# 2017_CARTE_PUISSANCE.net
KiCad netlist of a schematic drawn in Altium Designer
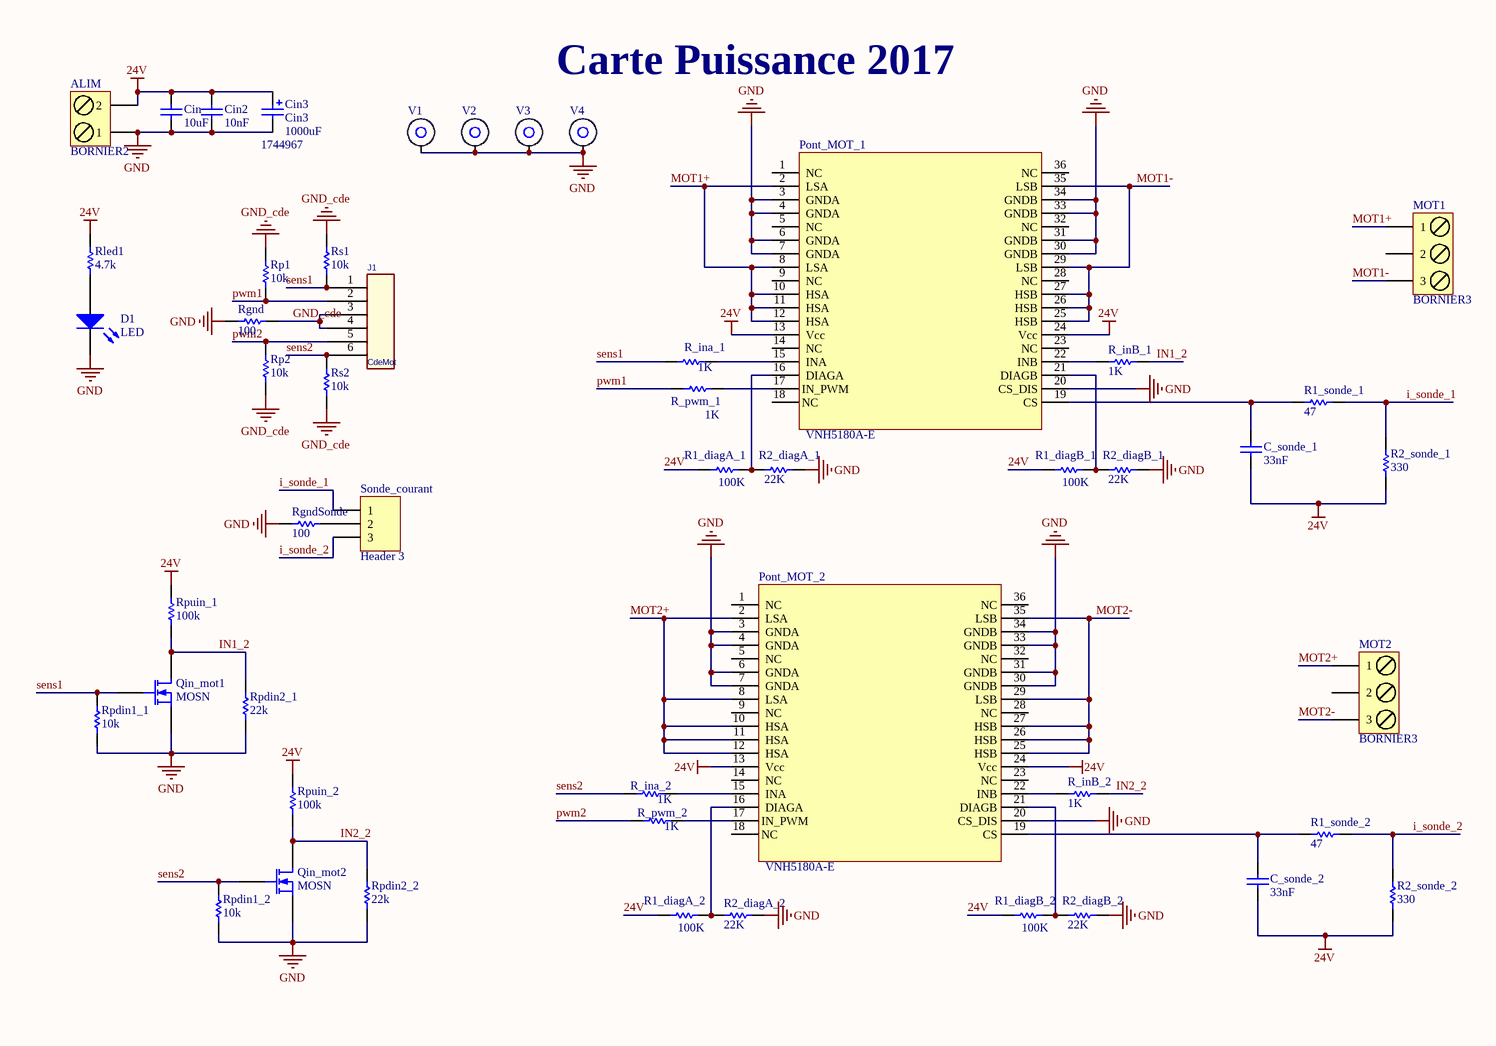
[diagram p0: 2017_CARTE_PUISSANCE.SchDoc, left]
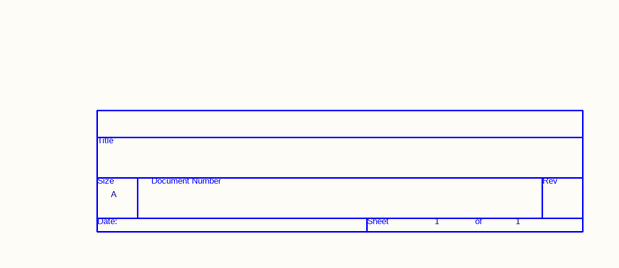
[diagram p1: 2017_CARTE_PUISSANCE.SchDoc, right]

(export (version "E")
  (design (tool "Eeschema 10.0.6"))
  (components
    (comp (ref "*")
      (value "TitleBlock0")
      (fields (field (name "PAGE COUNT") "1") (field (name "PAGE NUMBER") "1") (field (name "PAGE SIZE") "A"))
      (libsource (lib "*") (part "TitleBlock0"))
    )
    (comp (ref "ALIM")
      (value "BORNIER2")
      (footprint "BORNIER2_MALE_DROIT")
      (description "Terminal blocks, 2 pins, pitch=5mm")
      (libsource (lib "Robot2010") (part "BORNIER2"))
    )
    (comp (ref "Cin")
      (value "10uF")
      (footprint "C1206_N")
      (description "Capacitor")
      (fields (field (name "PUBLISHER") "Altium Limited"))
      (libsource (lib "DG_Condensateur") (part "Capacitor"))
    )
    (comp (ref "Cin2")
      (value "10nF")
      (footprint "C0805_N")
      (description "Capacitor")
      (fields (field (name "PUBLISHER") "Altium Limited"))
      (libsource (lib "DG_Condensateur") (part "Capacitor"))
    )
    (comp (ref "Cin3")
      (value "Cin3")
      (footprint "COND_POL_RAD_5.08B")
      (description "Polarized Capacitor")
      (fields
        (field (name "ALTIUM_VALUE") "1000uF")
        (field (name "FAR") "1744967")
        (field (name "PUBLISHER") "Altium Limited")
      )
      (libsource (lib "Robot2010") (part "CONDENSATEUR_POLARISE"))
    )
    (comp (ref "C_sonde_1")
      (value "33nF")
      (footprint "C0603_N")
      (description "Capacitor")
      (fields (field (name "PUBLISHER") "Altium Limited"))
      (libsource (lib "_ROBOT") (part "Condensateur"))
    )
    (comp (ref "C_sonde_2")
      (value "33nF")
      (footprint "C0603_N")
      (description "Capacitor")
      (fields (field (name "PUBLISHER") "Altium Limited"))
      (libsource (lib "_ROBOT") (part "Condensateur"))
    )
    (comp (ref "D1")
      (value "LED")
      (footprint "LED_0805")
      (description "Typical LED")
      (fields (field (name "PUBLISHER") "Altium Limited"))
      (libsource (lib "DG_LED") (part "LED"))
    )
    (comp (ref "J1") (value "CdeMot") (footprint "RJ11_6/6") (libsource (lib "*") (part "CONNECTEUR_RJ12")))
    (comp (ref "MOT1")
      (value "BORNIER3")
      (footprint "BORNIER3")
      (description "Terminal blocks, 2 pins, pitch=5mm")
      (libsource (lib "Connecteur") (part "BORNIER3"))
    )
    (comp (ref "MOT2")
      (value "BORNIER3")
      (footprint "BORNIER3")
      (description "Terminal blocks, 2 pins, pitch=5mm")
      (libsource (lib "Connecteur") (part "BORNIER3"))
    )
    (comp (ref "Pont_MOT_1")
      (value "VNH5180A-E")
      (footprint "PowerSSO-36 TP")
      (fields (field (name "TYPE") "VNH5180A-E"))
      (libsource (lib "Circuit intégré") (part "VNH5180A-E"))
    )
    (comp (ref "Pont_MOT_2")
      (value "VNH5180A-E")
      (footprint "PowerSSO-36 TP")
      (fields (field (name "TYPE") "VNH5180A-E"))
      (libsource (lib "Circuit intégré") (part "VNH5180A-E"))
    )
    (comp (ref "Qin_mot1")
      (value "MOSN")
      (footprint "SOT23-3N")
      (description "N-Channel MOSFET")
      (fields (field (name "PUBLISHER") "Altium Limited"))
      (libsource (lib "_ROBOT") (part "Transistor MOSFET-N"))
    )
    (comp (ref "Qin_mot2")
      (value "MOSN")
      (footprint "SOT23-3N")
      (description "N-Channel MOSFET")
      (fields (field (name "PUBLISHER") "Altium Limited"))
      (libsource (lib "_ROBOT") (part "Transistor MOSFET-N"))
    )
    (comp (ref "R1_diagA_1")
      (value "100K")
      (footprint "R1206_N")
      (description "Resistor")
      (fields (field (name "PUBLISHER") "Altium Limited"))
      (libsource (lib "_ROBOT") (part "Resistor"))
    )
    (comp (ref "R1_diagA_2")
      (value "100K")
      (footprint "R1206_N")
      (description "Resistor")
      (fields (field (name "PUBLISHER") "Altium Limited"))
      (libsource (lib "_ROBOT") (part "Resistor"))
    )
    (comp (ref "R1_diagB_1")
      (value "100K")
      (footprint "R1206_N")
      (description "Resistor")
      (fields (field (name "PUBLISHER") "Altium Limited"))
      (libsource (lib "_ROBOT") (part "Resistor"))
    )
    (comp (ref "R1_diagB_2")
      (value "100K")
      (footprint "R1206_N")
      (description "Resistor")
      (fields (field (name "PUBLISHER") "Altium Limited"))
      (libsource (lib "_ROBOT") (part "Resistor"))
    )
    (comp (ref "R1_sonde_1")
      (value "47")
      (footprint "R1206_N")
      (description "Resistor")
      (fields (field (name "PUBLISHER") "Altium Limited"))
      (libsource (lib "_ROBOT") (part "Resistor"))
    )
    (comp (ref "R1_sonde_2")
      (value "47")
      (footprint "R1206_N")
      (description "Resistor")
      (fields (field (name "PUBLISHER") "Altium Limited"))
      (libsource (lib "_ROBOT") (part "Resistor"))
    )
    (comp (ref "R2_diagA_1")
      (value "22K")
      (footprint "R1206_N")
      (description "Resistor")
      (fields (field (name "PUBLISHER") "Altium Limited"))
      (libsource (lib "_ROBOT") (part "Resistor"))
    )
    (comp (ref "R2_diagA_2")
      (value "22K")
      (footprint "R1206_N")
      (description "Resistor")
      (fields (field (name "PUBLISHER") "Altium Limited"))
      (libsource (lib "_ROBOT") (part "Resistor"))
    )
    (comp (ref "R2_diagB_1")
      (value "22K")
      (footprint "R1206_N")
      (description "Resistor")
      (fields (field (name "PUBLISHER") "Altium Limited"))
      (libsource (lib "_ROBOT") (part "Resistor"))
    )
    (comp (ref "R2_diagB_2")
      (value "22K")
      (footprint "R1206_N")
      (description "Resistor")
      (fields (field (name "PUBLISHER") "Altium Limited"))
      (libsource (lib "_ROBOT") (part "Resistor"))
    )
    (comp (ref "R2_sonde_1")
      (value "330")
      (footprint "R1206_N")
      (description "Resistor")
      (fields (field (name "PUBLISHER") "Altium Limited"))
      (libsource (lib "_ROBOT") (part "Resistor"))
    )
    (comp (ref "R2_sonde_2")
      (value "330")
      (footprint "R1206_N")
      (description "Resistor")
      (fields (field (name "PUBLISHER") "Altium Limited"))
      (libsource (lib "_ROBOT") (part "Resistor"))
    )
    (comp (ref "Rgnd")
      (value "100")
      (footprint "R1206_N")
      (description "Resistor")
      (fields (field (name "PUBLISHER") "Altium Limited"))
      (libsource (lib "DG_Resistance") (part "Resistor"))
    )
    (comp (ref "RgndSonde")
      (value "100")
      (footprint "R1206_N")
      (description "Resistor")
      (fields (field (name "PUBLISHER") "Altium Limited"))
      (libsource (lib "DG_Resistance") (part "Resistor"))
    )
    (comp (ref "Rled1")
      (value "4.7k")
      (footprint "R1206_N")
      (description "Resistor")
      (fields (field (name "PUBLISHER") "Altium Limited"))
      (libsource (lib "DG_Resistance") (part "Resistor"))
    )
    (comp (ref "Rp1")
      (value "10k")
      (footprint "R1206_N")
      (description "Resistor")
      (fields (field (name "PUBLISHER") "Altium Limited"))
      (libsource (lib "DG_Resistance") (part "Resistor"))
    )
    (comp (ref "Rp2")
      (value "10k")
      (footprint "R1206_N")
      (description "Resistor")
      (fields (field (name "PUBLISHER") "Altium Limited"))
      (libsource (lib "DG_Resistance") (part "Resistor"))
    )
    (comp (ref "Rpdin1_1")
      (value "10k")
      (footprint "R1206_N")
      (description "Resistor")
      (fields (field (name "PUBLISHER") "Altium Limited"))
      (libsource (lib "DG_Resistance") (part "Resistor"))
    )
    (comp (ref "Rpdin1_2")
      (value "10k")
      (footprint "R1206_N")
      (description "Resistor")
      (fields (field (name "PUBLISHER") "Altium Limited"))
      (libsource (lib "DG_Resistance") (part "Resistor"))
    )
    (comp (ref "Rpdin2_1")
      (value "22k")
      (footprint "R1206_N")
      (description "Resistor")
      (fields (field (name "PUBLISHER") "Altium Limited"))
      (libsource (lib "DG_Resistance") (part "Resistor"))
    )
    (comp (ref "Rpdin2_2")
      (value "22k")
      (footprint "R1206_N")
      (description "Resistor")
      (fields (field (name "PUBLISHER") "Altium Limited"))
      (libsource (lib "DG_Resistance") (part "Resistor"))
    )
    (comp (ref "Rpuin_1")
      (value "100k")
      (footprint "R1206_N")
      (description "Resistor")
      (fields (field (name "PUBLISHER") "Altium Limited"))
      (libsource (lib "DG_Resistance") (part "Resistor"))
    )
    (comp (ref "Rpuin_2")
      (value "100k")
      (footprint "R1206_N")
      (description "Resistor")
      (fields (field (name "PUBLISHER") "Altium Limited"))
      (libsource (lib "DG_Resistance") (part "Resistor"))
    )
    (comp (ref "Rs1")
      (value "10k")
      (footprint "R1206_N")
      (description "Resistor")
      (fields (field (name "PUBLISHER") "Altium Limited"))
      (libsource (lib "DG_Resistance") (part "Resistor"))
    )
    (comp (ref "Rs2")
      (value "10k")
      (footprint "R1206_N")
      (description "Resistor")
      (fields (field (name "PUBLISHER") "Altium Limited"))
      (libsource (lib "DG_Resistance") (part "Resistor"))
    )
    (comp (ref "R_ina_1")
      (value "1K")
      (footprint "R1206_N")
      (description "Resistor")
      (fields (field (name "PUBLISHER") "Altium Limited"))
      (libsource (lib "_ROBOT") (part "Resistor"))
    )
    (comp (ref "R_ina_2")
      (value "1K")
      (footprint "R1206_N")
      (description "Resistor")
      (fields (field (name "PUBLISHER") "Altium Limited"))
      (libsource (lib "_ROBOT") (part "Resistor"))
    )
    (comp (ref "R_inB_1")
      (value "1K")
      (footprint "R1206_N")
      (description "Resistor")
      (fields (field (name "PUBLISHER") "Altium Limited"))
      (libsource (lib "_ROBOT") (part "Resistor"))
    )
    (comp (ref "R_inB_2")
      (value "1K")
      (footprint "R1206_N")
      (description "Resistor")
      (fields (field (name "PUBLISHER") "Altium Limited"))
      (libsource (lib "_ROBOT") (part "Resistor"))
    )
    (comp (ref "R_pwm_1")
      (value "1K")
      (footprint "R1206_N")
      (description "Resistor")
      (fields (field (name "PUBLISHER") "Altium Limited"))
      (libsource (lib "_ROBOT") (part "Resistor"))
    )
    (comp (ref "R_pwm_2")
      (value "1K")
      (footprint "R1206_N")
      (description "Resistor")
      (fields (field (name "PUBLISHER") "Altium Limited"))
      (libsource (lib "_ROBOT") (part "Resistor"))
    )
    (comp (ref "Sonde_courant")
      (value "Header 3")
      (footprint "HDR1X3")
      (description "Header, 3-Pin")
      (fields (field (name "PUBLISHER") "Altium Limited"))
      (libsource (lib "DG_Connecteur") (part "Header 3"))
    )
    (comp (ref "V1")
      (value "Entretoise WURTH CMS")
      (footprint "ENTRETOISE_CMS")
      (description "Entretoise Wurth")
      (fields (field (name "PUBLISHER") "Damien Guitton"))
      (libsource (lib "_ROBOT") (part "Entretoise WURTH CMS"))
    )
    (comp (ref "V2")
      (value "Entretoise WURTH CMS")
      (footprint "ENTRETOISE_CMS")
      (description "Entretoise Wurth")
      (fields (field (name "PUBLISHER") "Damien Guitton"))
      (libsource (lib "_ROBOT") (part "Entretoise WURTH CMS"))
    )
    (comp (ref "V3")
      (value "Entretoise WURTH CMS")
      (footprint "ENTRETOISE_CMS")
      (description "Entretoise Wurth")
      (fields (field (name "PUBLISHER") "Damien Guitton"))
      (libsource (lib "_ROBOT") (part "Entretoise WURTH CMS"))
    )
    (comp (ref "V4")
      (value "Entretoise WURTH CMS")
      (footprint "ENTRETOISE_CMS")
      (description "Entretoise Wurth")
      (fields (field (name "PUBLISHER") "Damien Guitton"))
      (libsource (lib "_ROBOT") (part "Entretoise WURTH CMS"))
    )
  )
  (nets
    (net (code "1") (name "/IN1_2") (class "Default")
      (node (ref "Qin_mot1") (pin "3") (pinfunction "D_3") (pintype "passive"))
      (node (ref "R_inB_1") (pin "2") (pinfunction "2_2") (pintype "passive"))
      (node (ref "Rpdin2_1") (pin "2") (pinfunction "2_2") (pintype "passive"))
      (node (ref "Rpuin_1") (pin "1") (pinfunction "1_1") (pintype "passive"))
    )
    (net (code "2") (name "/IN2_2") (class "Default")
      (node (ref "Qin_mot2") (pin "3") (pinfunction "D_3") (pintype "passive"))
      (node (ref "R_inB_2") (pin "2") (pinfunction "2_2") (pintype "passive"))
      (node (ref "Rpdin2_2") (pin "2") (pinfunction "2_2") (pintype "passive"))
      (node (ref "Rpuin_2") (pin "1") (pinfunction "1_1") (pintype "passive"))
    )
    (net (code "3") (name "/MOT1+") (class "Default")
      (node (ref "MOT1") (pin "1") (pinfunction "1_1") (pintype "passive"))
      (node (ref "Pont_MOT_1") (pin "10") (pinfunction "HSA_10") (pintype "passive"))
      (node (ref "Pont_MOT_1") (pin "11") (pinfunction "HSA_11") (pintype "passive"))
      (node (ref "Pont_MOT_1") (pin "12") (pinfunction "HSA_12") (pintype "passive"))
      (node (ref "Pont_MOT_1") (pin "2") (pinfunction "LSA_2") (pintype "passive"))
      (node (ref "Pont_MOT_1") (pin "8") (pinfunction "LSA_8") (pintype "passive"))
    )
    (net (code "4") (name "/MOT1-") (class "Default")
      (node (ref "MOT1") (pin "3") (pinfunction "3_3") (pintype "passive"))
      (node (ref "Pont_MOT_1") (pin "25") (pinfunction "HSB_25") (pintype "passive"))
      (node (ref "Pont_MOT_1") (pin "26") (pinfunction "HSB_26") (pintype "passive"))
      (node (ref "Pont_MOT_1") (pin "27") (pinfunction "HSB_27") (pintype "passive"))
      (node (ref "Pont_MOT_1") (pin "29") (pinfunction "LSB_29") (pintype "passive"))
      (node (ref "Pont_MOT_1") (pin "35") (pinfunction "LSB_35") (pintype "passive"))
    )
    (net (code "5") (name "/MOT2+") (class "Default")
      (node (ref "MOT2") (pin "1") (pinfunction "1_1") (pintype "passive"))
      (node (ref "Pont_MOT_2") (pin "10") (pinfunction "HSA_10") (pintype "passive"))
      (node (ref "Pont_MOT_2") (pin "11") (pinfunction "HSA_11") (pintype "passive"))
      (node (ref "Pont_MOT_2") (pin "12") (pinfunction "HSA_12") (pintype "passive"))
      (node (ref "Pont_MOT_2") (pin "2") (pinfunction "LSA_2") (pintype "passive"))
      (node (ref "Pont_MOT_2") (pin "8") (pinfunction "LSA_8") (pintype "passive"))
    )
    (net (code "6") (name "/MOT2-") (class "Default")
      (node (ref "MOT2") (pin "3") (pinfunction "3_3") (pintype "passive"))
      (node (ref "Pont_MOT_2") (pin "25") (pinfunction "HSB_25") (pintype "passive"))
      (node (ref "Pont_MOT_2") (pin "26") (pinfunction "HSB_26") (pintype "passive"))
      (node (ref "Pont_MOT_2") (pin "27") (pinfunction "HSB_27") (pintype "passive"))
      (node (ref "Pont_MOT_2") (pin "29") (pinfunction "LSB_29") (pintype "passive"))
      (node (ref "Pont_MOT_2") (pin "35") (pinfunction "LSB_35") (pintype "passive"))
    )
    (net (code "7") (name "/i_sonde_1") (class "Default")
      (node (ref "R1_sonde_1") (pin "2") (pinfunction "2_2") (pintype "passive"))
      (node (ref "R2_sonde_1") (pin "2") (pinfunction "2_2") (pintype "passive"))
      (node (ref "Sonde_courant") (pin "1") (pinfunction "1_1") (pintype "passive"))
    )
    (net (code "8") (name "/i_sonde_2") (class "Default")
      (node (ref "R1_sonde_2") (pin "2") (pinfunction "2_2") (pintype "passive"))
      (node (ref "R2_sonde_2") (pin "2") (pinfunction "2_2") (pintype "passive"))
      (node (ref "Sonde_courant") (pin "3") (pinfunction "3_3") (pintype "passive"))
    )
    (net (code "9") (name "/pwm1") (class "Default")
      (node (ref "J1") (pin "2") (pinfunction "2_2") (pintype "passive"))
      (node (ref "R_pwm_1") (pin "1") (pinfunction "1_1") (pintype "passive"))
      (node (ref "Rp1") (pin "1") (pinfunction "1_1") (pintype "passive"))
    )
    (net (code "10") (name "/pwm2") (class "Default")
      (node (ref "J1") (pin "5") (pinfunction "5_5") (pintype "passive"))
      (node (ref "R_pwm_2") (pin "1") (pinfunction "1_1") (pintype "passive"))
      (node (ref "Rp2") (pin "2") (pinfunction "2_2") (pintype "passive"))
    )
    (net (code "11") (name "/sens1") (class "Default")
      (node (ref "J1") (pin "1") (pinfunction "1_1") (pintype "passive"))
      (node (ref "Qin_mot1") (pin "1") (pinfunction "G_1") (pintype "passive"))
      (node (ref "R_ina_1") (pin "1") (pinfunction "1_1") (pintype "passive"))
      (node (ref "Rpdin1_1") (pin "1") (pinfunction "1_1") (pintype "passive"))
      (node (ref "Rs1") (pin "1") (pinfunction "1_1") (pintype "passive"))
    )
    (net (code "12") (name "/sens2") (class "Default")
      (node (ref "J1") (pin "6") (pinfunction "6_6") (pintype "passive"))
      (node (ref "Qin_mot2") (pin "1") (pinfunction "G_1") (pintype "passive"))
      (node (ref "R_ina_2") (pin "1") (pinfunction "1_1") (pintype "passive"))
      (node (ref "Rpdin1_2") (pin "1") (pinfunction "1_1") (pintype "passive"))
      (node (ref "Rs2") (pin "2") (pinfunction "2_2") (pintype "passive"))
    )
    (net (code "13") (name "24V") (class "Default")
      (node (ref "ALIM") (pin "2") (pinfunction "2_2") (pintype "passive"))
      (node (ref "C_sonde_1") (pin "1") (pinfunction "1_1") (pintype "passive"))
      (node (ref "C_sonde_2") (pin "1") (pinfunction "1_1") (pintype "passive"))
      (node (ref "Cin") (pin "2") (pinfunction "2_2") (pintype "passive"))
      (node (ref "Cin2") (pin "2") (pinfunction "2_2") (pintype "passive"))
      (node (ref "Cin3") (pin "1") (pinfunction "1_1") (pintype "passive"))
      (node (ref "Pont_MOT_1") (pin "13") (pinfunction "Vcc_13") (pintype "passive"))
      (node (ref "Pont_MOT_1") (pin "24") (pinfunction "Vcc_24") (pintype "passive"))
      (node (ref "Pont_MOT_2") (pin "13") (pinfunction "Vcc_13") (pintype "passive"))
      (node (ref "Pont_MOT_2") (pin "24") (pinfunction "Vcc_24") (pintype "passive"))
      (node (ref "R1_diagA_1") (pin "1") (pinfunction "1_1") (pintype "passive"))
      (node (ref "R1_diagA_2") (pin "1") (pinfunction "1_1") (pintype "passive"))
      (node (ref "R1_diagB_1") (pin "1") (pinfunction "1_1") (pintype "passive"))
      (node (ref "R1_diagB_2") (pin "1") (pinfunction "1_1") (pintype "passive"))
      (node (ref "R2_sonde_1") (pin "1") (pinfunction "1_1") (pintype "passive"))
      (node (ref "R2_sonde_2") (pin "1") (pinfunction "1_1") (pintype "passive"))
      (node (ref "Rled1") (pin "2") (pinfunction "2_2") (pintype "passive"))
      (node (ref "Rpuin_1") (pin "2") (pinfunction "2_2") (pintype "passive"))
      (node (ref "Rpuin_2") (pin "2") (pinfunction "2_2") (pintype "passive"))
    )
    (net (code "14") (name "GND") (class "Default")
      (node (ref "ALIM") (pin "1") (pinfunction "1_1") (pintype "passive"))
      (node (ref "Cin") (pin "1") (pinfunction "1_1") (pintype "passive"))
      (node (ref "Cin2") (pin "1") (pinfunction "1_1") (pintype "passive"))
      (node (ref "Cin3") (pin "2") (pinfunction "2_2") (pintype "passive"))
      (node (ref "D1") (pin "2") (pinfunction "2_2") (pintype "passive"))
      (node (ref "Pont_MOT_1") (pin "20") (pinfunction "CS_DIS_20") (pintype "passive"))
      (node (ref "Pont_MOT_1") (pin "3") (pinfunction "GNDA_3") (pintype "passive"))
      (node (ref "Pont_MOT_1") (pin "30") (pinfunction "GNDB_30") (pintype "passive"))
      (node (ref "Pont_MOT_1") (pin "31") (pinfunction "GNDB_31") (pintype "passive"))
      (node (ref "Pont_MOT_1") (pin "33") (pinfunction "GNDB_33") (pintype "passive"))
      (node (ref "Pont_MOT_1") (pin "34") (pinfunction "GNDB_34") (pintype "passive"))
      (node (ref "Pont_MOT_1") (pin "4") (pinfunction "GNDA_4") (pintype "passive"))
      (node (ref "Pont_MOT_1") (pin "6") (pinfunction "GNDA_6") (pintype "passive"))
      (node (ref "Pont_MOT_1") (pin "7") (pinfunction "GNDA_7") (pintype "passive"))
      (node (ref "Pont_MOT_2") (pin "20") (pinfunction "CS_DIS_20") (pintype "passive"))
      (node (ref "Pont_MOT_2") (pin "3") (pinfunction "GNDA_3") (pintype "passive"))
      (node (ref "Pont_MOT_2") (pin "30") (pinfunction "GNDB_30") (pintype "passive"))
      (node (ref "Pont_MOT_2") (pin "31") (pinfunction "GNDB_31") (pintype "passive"))
      (node (ref "Pont_MOT_2") (pin "33") (pinfunction "GNDB_33") (pintype "passive"))
      (node (ref "Pont_MOT_2") (pin "34") (pinfunction "GNDB_34") (pintype "passive"))
      (node (ref "Pont_MOT_2") (pin "4") (pinfunction "GNDA_4") (pintype "passive"))
      (node (ref "Pont_MOT_2") (pin "6") (pinfunction "GNDA_6") (pintype "passive"))
      (node (ref "Pont_MOT_2") (pin "7") (pinfunction "GNDA_7") (pintype "passive"))
      (node (ref "Qin_mot1") (pin "2") (pinfunction "S_2") (pintype "passive"))
      (node (ref "Qin_mot2") (pin "2") (pinfunction "S_2") (pintype "passive"))
      (node (ref "R2_diagA_1") (pin "2") (pinfunction "2_2") (pintype "passive"))
      (node (ref "R2_diagA_2") (pin "2") (pinfunction "2_2") (pintype "passive"))
      (node (ref "R2_diagB_1") (pin "2") (pinfunction "2_2") (pintype "passive"))
      (node (ref "R2_diagB_2") (pin "2") (pinfunction "2_2") (pintype "passive"))
      (node (ref "Rgnd") (pin "2") (pinfunction "2_2") (pintype "passive"))
      (node (ref "RgndSonde") (pin "2") (pinfunction "2_2") (pintype "passive"))
      (node (ref "Rpdin1_1") (pin "2") (pinfunction "2_2") (pintype "passive"))
      (node (ref "Rpdin1_2") (pin "2") (pinfunction "2_2") (pintype "passive"))
      (node (ref "Rpdin2_1") (pin "1") (pinfunction "1_1") (pintype "passive"))
      (node (ref "Rpdin2_2") (pin "1") (pinfunction "1_1") (pintype "passive"))
      (node (ref "V1") (pin "1") (pinfunction "1_1") (pintype "passive"))
      (node (ref "V2") (pin "1") (pinfunction "1_1") (pintype "passive"))
      (node (ref "V3") (pin "1") (pinfunction "1_1") (pintype "passive"))
      (node (ref "V4") (pin "1") (pinfunction "1_1") (pintype "passive"))
    )
    (net (code "15") (name "GND_cde") (class "Default")
      (node (ref "J1") (pin "3") (pinfunction "3_3") (pintype "passive"))
      (node (ref "J1") (pin "4") (pinfunction "4_4") (pintype "passive"))
      (node (ref "Rgnd") (pin "1") (pinfunction "1_1") (pintype "passive"))
      (node (ref "Rp1") (pin "2") (pinfunction "2_2") (pintype "passive"))
      (node (ref "Rp2") (pin "1") (pinfunction "1_1") (pintype "passive"))
      (node (ref "Rs1") (pin "2") (pinfunction "2_2") (pintype "passive"))
      (node (ref "Rs2") (pin "1") (pinfunction "1_1") (pintype "passive"))
    )
    (net (code "16") (name "Net-(D1-Pad1)") (class "Default")
      (node (ref "D1") (pin "1") (pinfunction "1_1") (pintype "passive"))
      (node (ref "Rled1") (pin "1") (pinfunction "1_1") (pintype "passive"))
    )
    (net (code "17") (name "Net-(Pont_MOT_1-CS)") (class "Default")
      (node (ref "C_sonde_1") (pin "2") (pinfunction "2_2") (pintype "passive"))
      (node (ref "Pont_MOT_1") (pin "19") (pinfunction "CS_19") (pintype "passive"))
      (node (ref "R1_sonde_1") (pin "1") (pinfunction "1_1") (pintype "passive"))
    )
    (net (code "18") (name "Net-(Pont_MOT_1-DIAGA)") (class "Default")
      (node (ref "Pont_MOT_1") (pin "16") (pinfunction "DIAGA_16") (pintype "passive"))
      (node (ref "R1_diagA_1") (pin "2") (pinfunction "2_2") (pintype "passive"))
      (node (ref "R2_diagA_1") (pin "1") (pinfunction "1_1") (pintype "passive"))
    )
    (net (code "19") (name "Net-(Pont_MOT_1-DIAGB)") (class "Default")
      (node (ref "Pont_MOT_1") (pin "21") (pinfunction "DIAGB_21") (pintype "passive"))
      (node (ref "R1_diagB_1") (pin "2") (pinfunction "2_2") (pintype "passive"))
      (node (ref "R2_diagB_1") (pin "1") (pinfunction "1_1") (pintype "passive"))
    )
    (net (code "20") (name "Net-(Pont_MOT_1-INA)") (class "Default")
      (node (ref "Pont_MOT_1") (pin "15") (pinfunction "INA_15") (pintype "passive"))
      (node (ref "R_ina_1") (pin "2") (pinfunction "2_2") (pintype "passive"))
    )
    (net (code "21") (name "Net-(Pont_MOT_1-INB)") (class "Default")
      (node (ref "Pont_MOT_1") (pin "22") (pinfunction "INB_22") (pintype "passive"))
      (node (ref "R_inB_1") (pin "1") (pinfunction "1_1") (pintype "passive"))
    )
    (net (code "22") (name "Net-(Pont_MOT_1-IN_PWM)") (class "Default")
      (node (ref "Pont_MOT_1") (pin "17") (pinfunction "IN_PWM_17") (pintype "passive"))
      (node (ref "R_pwm_1") (pin "2") (pinfunction "2_2") (pintype "passive"))
    )
    (net (code "23") (name "Net-(Pont_MOT_2-CS)") (class "Default")
      (node (ref "C_sonde_2") (pin "2") (pinfunction "2_2") (pintype "passive"))
      (node (ref "Pont_MOT_2") (pin "19") (pinfunction "CS_19") (pintype "passive"))
      (node (ref "R1_sonde_2") (pin "1") (pinfunction "1_1") (pintype "passive"))
    )
    (net (code "24") (name "Net-(Pont_MOT_2-DIAGA)") (class "Default")
      (node (ref "Pont_MOT_2") (pin "16") (pinfunction "DIAGA_16") (pintype "passive"))
      (node (ref "R1_diagA_2") (pin "2") (pinfunction "2_2") (pintype "passive"))
      (node (ref "R2_diagA_2") (pin "1") (pinfunction "1_1") (pintype "passive"))
    )
    (net (code "25") (name "Net-(Pont_MOT_2-DIAGB)") (class "Default")
      (node (ref "Pont_MOT_2") (pin "21") (pinfunction "DIAGB_21") (pintype "passive"))
      (node (ref "R1_diagB_2") (pin "2") (pinfunction "2_2") (pintype "passive"))
      (node (ref "R2_diagB_2") (pin "1") (pinfunction "1_1") (pintype "passive"))
    )
    (net (code "26") (name "Net-(Pont_MOT_2-INA)") (class "Default")
      (node (ref "Pont_MOT_2") (pin "15") (pinfunction "INA_15") (pintype "passive"))
      (node (ref "R_ina_2") (pin "2") (pinfunction "2_2") (pintype "passive"))
    )
    (net (code "27") (name "Net-(Pont_MOT_2-INB)") (class "Default")
      (node (ref "Pont_MOT_2") (pin "22") (pinfunction "INB_22") (pintype "passive"))
      (node (ref "R_inB_2") (pin "1") (pinfunction "1_1") (pintype "passive"))
    )
    (net (code "28") (name "Net-(Pont_MOT_2-IN_PWM)") (class "Default")
      (node (ref "Pont_MOT_2") (pin "17") (pinfunction "IN_PWM_17") (pintype "passive"))
      (node (ref "R_pwm_2") (pin "2") (pinfunction "2_2") (pintype "passive"))
    )
    (net (code "29") (name "Net-(RgndSonde-Pad1)") (class "Default")
      (node (ref "RgndSonde") (pin "1") (pinfunction "1_1") (pintype "passive"))
      (node (ref "Sonde_courant") (pin "2") (pinfunction "2_2") (pintype "passive"))
    )
    (net (code "30") (name "unconnected-(MOT1-Pad2)") (class "Default")
      (node (ref "MOT1") (pin "2") (pinfunction "2_2") (pintype "passive"))
    )
    (net (code "31") (name "unconnected-(MOT2-Pad2)") (class "Default")
      (node (ref "MOT2") (pin "2") (pinfunction "2_2") (pintype "passive"))
    )
    (net (code "32") (name "unconnected-(Pont_MOT_1-NC-Pad1)") (class "Default")
      (node (ref "Pont_MOT_1") (pin "1") (pinfunction "NC_1") (pintype "passive"))
    )
    (net (code "33") (name "unconnected-(Pont_MOT_1-NC-Pad5)") (class "Default")
      (node (ref "Pont_MOT_1") (pin "5") (pinfunction "NC_5") (pintype "passive"))
    )
    (net (code "34") (name "unconnected-(Pont_MOT_1-NC-Pad9)") (class "Default")
      (node (ref "Pont_MOT_1") (pin "9") (pinfunction "NC_9") (pintype "passive"))
    )
    (net (code "35") (name "unconnected-(Pont_MOT_1-NC-Pad14)") (class "Default")
      (node (ref "Pont_MOT_1") (pin "14") (pinfunction "NC_14") (pintype "passive"))
    )
    (net (code "36") (name "unconnected-(Pont_MOT_1-NC-Pad18)") (class "Default")
      (node (ref "Pont_MOT_1") (pin "18") (pinfunction "NC_18") (pintype "passive"))
    )
    (net (code "37") (name "unconnected-(Pont_MOT_1-NC-Pad23)") (class "Default")
      (node (ref "Pont_MOT_1") (pin "23") (pinfunction "NC_23") (pintype "passive"))
    )
    (net (code "38") (name "unconnected-(Pont_MOT_1-NC-Pad28)") (class "Default")
      (node (ref "Pont_MOT_1") (pin "28") (pinfunction "NC_28") (pintype "passive"))
    )
    (net (code "39") (name "unconnected-(Pont_MOT_1-NC-Pad32)") (class "Default")
      (node (ref "Pont_MOT_1") (pin "32") (pinfunction "NC_32") (pintype "passive"))
    )
    (net (code "40") (name "unconnected-(Pont_MOT_1-NC-Pad36)") (class "Default")
      (node (ref "Pont_MOT_1") (pin "36") (pinfunction "NC_36") (pintype "passive"))
    )
    (net (code "41") (name "unconnected-(Pont_MOT_2-NC-Pad1)") (class "Default")
      (node (ref "Pont_MOT_2") (pin "1") (pinfunction "NC_1") (pintype "passive"))
    )
    (net (code "42") (name "unconnected-(Pont_MOT_2-NC-Pad5)") (class "Default")
      (node (ref "Pont_MOT_2") (pin "5") (pinfunction "NC_5") (pintype "passive"))
    )
    (net (code "43") (name "unconnected-(Pont_MOT_2-NC-Pad9)") (class "Default")
      (node (ref "Pont_MOT_2") (pin "9") (pinfunction "NC_9") (pintype "passive"))
    )
    (net (code "44") (name "unconnected-(Pont_MOT_2-NC-Pad14)") (class "Default")
      (node (ref "Pont_MOT_2") (pin "14") (pinfunction "NC_14") (pintype "passive"))
    )
    (net (code "45") (name "unconnected-(Pont_MOT_2-NC-Pad18)") (class "Default")
      (node (ref "Pont_MOT_2") (pin "18") (pinfunction "NC_18") (pintype "passive"))
    )
    (net (code "46") (name "unconnected-(Pont_MOT_2-NC-Pad23)") (class "Default")
      (node (ref "Pont_MOT_2") (pin "23") (pinfunction "NC_23") (pintype "passive"))
    )
    (net (code "47") (name "unconnected-(Pont_MOT_2-NC-Pad28)") (class "Default")
      (node (ref "Pont_MOT_2") (pin "28") (pinfunction "NC_28") (pintype "passive"))
    )
    (net (code "48") (name "unconnected-(Pont_MOT_2-NC-Pad32)") (class "Default")
      (node (ref "Pont_MOT_2") (pin "32") (pinfunction "NC_32") (pintype "passive"))
    )
    (net (code "49") (name "unconnected-(Pont_MOT_2-NC-Pad36)") (class "Default")
      (node (ref "Pont_MOT_2") (pin "36") (pinfunction "NC_36") (pintype "passive"))
    )
  )
)
